# LED_base_left.net
KiCad netlist of a schematic drawn in EAGLE
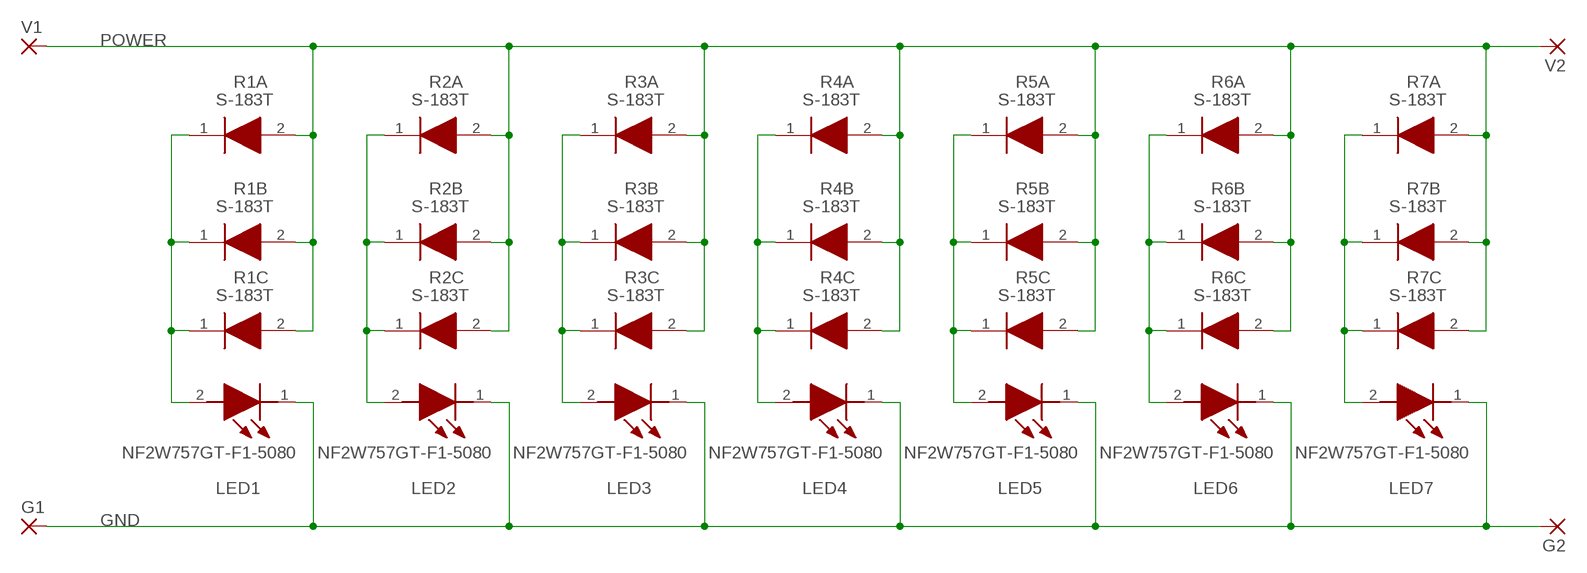
[diagram p0: schematic, sheet 1]

(export (version "E")
  (design (tool "Eeschema 10.0.6"))
  (components
    (comp (ref "G1")
      (value "SMD_FULL")
      (footprint "eagle-import:SMD3.5-2.5")
      (libsource (lib "eagle-import") (part "SMD_FULL"))
    )
    (comp (ref "G2")
      (value "SMD_HALF")
      (footprint "eagle-import:SMD1.75-2.5")
      (libsource (lib "eagle-import") (part "SMD_HALF"))
    )
    (comp (ref "LED1")
      (value "NF2W757GT-F1-5080")
      (footprint "eagle-import:NF2W757DRTX")
      (fields (field (name "RS_PART_NUMBER") "1372170"))
      (libsource (lib "eagle-import") (part "NF2W757GT-F1-5080"))
    )
    (comp (ref "LED2")
      (value "NF2W757GT-F1-5080")
      (footprint "eagle-import:NF2W757DRTX")
      (fields (field (name "RS_PART_NUMBER") "1372170"))
      (libsource (lib "eagle-import") (part "NF2W757GT-F1-5080"))
    )
    (comp (ref "LED3")
      (value "NF2W757GT-F1-5080")
      (footprint "eagle-import:NF2W757DRTX")
      (fields (field (name "RS_PART_NUMBER") "1372170"))
      (libsource (lib "eagle-import") (part "NF2W757GT-F1-5080"))
    )
    (comp (ref "LED4")
      (value "NF2W757GT-F1-5080")
      (footprint "eagle-import:NF2W757DRTX")
      (fields (field (name "RS_PART_NUMBER") "1372170"))
      (libsource (lib "eagle-import") (part "NF2W757GT-F1-5080"))
    )
    (comp (ref "LED5")
      (value "NF2W757GT-F1-5080")
      (footprint "eagle-import:NF2W757DRTX")
      (fields (field (name "RS_PART_NUMBER") "1372170"))
      (libsource (lib "eagle-import") (part "NF2W757GT-F1-5080"))
    )
    (comp (ref "LED6")
      (value "NF2W757GT-F1-5080")
      (footprint "eagle-import:NF2W757DRTX")
      (fields (field (name "RS_PART_NUMBER") "1372170"))
      (libsource (lib "eagle-import") (part "NF2W757GT-F1-5080"))
    )
    (comp (ref "LED7")
      (value "NF2W757GT-F1-5080")
      (footprint "eagle-import:NF2W757DRTX")
      (fields (field (name "RS_PART_NUMBER") "1372170"))
      (libsource (lib "eagle-import") (part "NF2W757GT-F1-5080"))
    )
    (comp (ref "R1A")
      (value "S-183T")
      (footprint "eagle-import:SODFL3516X70NX")
      (fields (field (name "MOUSER_PART_NUMBER") "954-S-183T"))
      (libsource (lib "eagle-import") (part "S-183T"))
    )
    (comp (ref "R1B")
      (value "S-183T")
      (footprint "eagle-import:SODFL3516X70NX")
      (fields (field (name "MOUSER_PART_NUMBER") "954-S-183T"))
      (libsource (lib "eagle-import") (part "S-183T"))
    )
    (comp (ref "R1C")
      (value "S-183T")
      (footprint "eagle-import:SODFL3516X70NX")
      (fields (field (name "MOUSER_PART_NUMBER") "954-S-183T"))
      (libsource (lib "eagle-import") (part "S-183T"))
    )
    (comp (ref "R2A")
      (value "S-183T")
      (footprint "eagle-import:SODFL3516X70NX")
      (fields (field (name "MOUSER_PART_NUMBER") "954-S-183T"))
      (libsource (lib "eagle-import") (part "S-183T"))
    )
    (comp (ref "R2B")
      (value "S-183T")
      (footprint "eagle-import:SODFL3516X70NX")
      (fields (field (name "MOUSER_PART_NUMBER") "954-S-183T"))
      (libsource (lib "eagle-import") (part "S-183T"))
    )
    (comp (ref "R2C")
      (value "S-183T")
      (footprint "eagle-import:SODFL3516X70NX")
      (fields (field (name "MOUSER_PART_NUMBER") "954-S-183T"))
      (libsource (lib "eagle-import") (part "S-183T"))
    )
    (comp (ref "R3A")
      (value "S-183T")
      (footprint "eagle-import:SODFL3516X70NX")
      (fields (field (name "MOUSER_PART_NUMBER") "954-S-183T"))
      (libsource (lib "eagle-import") (part "S-183T"))
    )
    (comp (ref "R3B")
      (value "S-183T")
      (footprint "eagle-import:SODFL3516X70NX")
      (fields (field (name "MOUSER_PART_NUMBER") "954-S-183T"))
      (libsource (lib "eagle-import") (part "S-183T"))
    )
    (comp (ref "R3C")
      (value "S-183T")
      (footprint "eagle-import:SODFL3516X70NX")
      (fields (field (name "MOUSER_PART_NUMBER") "954-S-183T"))
      (libsource (lib "eagle-import") (part "S-183T"))
    )
    (comp (ref "R4A")
      (value "S-183T")
      (footprint "eagle-import:SODFL3516X70NX")
      (fields (field (name "MOUSER_PART_NUMBER") "954-S-183T"))
      (libsource (lib "eagle-import") (part "S-183T"))
    )
    (comp (ref "R4B")
      (value "S-183T")
      (footprint "eagle-import:SODFL3516X70NX")
      (fields (field (name "MOUSER_PART_NUMBER") "954-S-183T"))
      (libsource (lib "eagle-import") (part "S-183T"))
    )
    (comp (ref "R4C")
      (value "S-183T")
      (footprint "eagle-import:SODFL3516X70NX")
      (fields (field (name "MOUSER_PART_NUMBER") "954-S-183T"))
      (libsource (lib "eagle-import") (part "S-183T"))
    )
    (comp (ref "R5A")
      (value "S-183T")
      (footprint "eagle-import:SODFL3516X70NX")
      (fields (field (name "MOUSER_PART_NUMBER") "954-S-183T"))
      (libsource (lib "eagle-import") (part "S-183T"))
    )
    (comp (ref "R5B")
      (value "S-183T")
      (footprint "eagle-import:SODFL3516X70NX")
      (fields (field (name "MOUSER_PART_NUMBER") "954-S-183T"))
      (libsource (lib "eagle-import") (part "S-183T"))
    )
    (comp (ref "R5C")
      (value "S-183T")
      (footprint "eagle-import:SODFL3516X70NX")
      (fields (field (name "MOUSER_PART_NUMBER") "954-S-183T"))
      (libsource (lib "eagle-import") (part "S-183T"))
    )
    (comp (ref "R6A")
      (value "S-183T")
      (footprint "eagle-import:SODFL3516X70NX")
      (fields (field (name "MOUSER_PART_NUMBER") "954-S-183T"))
      (libsource (lib "eagle-import") (part "S-183T"))
    )
    (comp (ref "R6B")
      (value "S-183T")
      (footprint "eagle-import:SODFL3516X70NX")
      (fields (field (name "MOUSER_PART_NUMBER") "954-S-183T"))
      (libsource (lib "eagle-import") (part "S-183T"))
    )
    (comp (ref "R6C")
      (value "S-183T")
      (footprint "eagle-import:SODFL3516X70NX")
      (fields (field (name "MOUSER_PART_NUMBER") "954-S-183T"))
      (libsource (lib "eagle-import") (part "S-183T"))
    )
    (comp (ref "R7A")
      (value "S-183T")
      (footprint "eagle-import:SODFL3516X70NX")
      (fields (field (name "MOUSER_PART_NUMBER") "954-S-183T"))
      (libsource (lib "eagle-import") (part "S-183T"))
    )
    (comp (ref "R7B")
      (value "S-183T")
      (footprint "eagle-import:SODFL3516X70NX")
      (fields (field (name "MOUSER_PART_NUMBER") "954-S-183T"))
      (libsource (lib "eagle-import") (part "S-183T"))
    )
    (comp (ref "R7C")
      (value "S-183T")
      (footprint "eagle-import:SODFL3516X70NX")
      (fields (field (name "MOUSER_PART_NUMBER") "954-S-183T"))
      (libsource (lib "eagle-import") (part "S-183T"))
    )
    (comp (ref "V1")
      (value "SMD_FULL")
      (footprint "eagle-import:SMD3.5-2.5")
      (libsource (lib "eagle-import") (part "SMD_FULL"))
    )
    (comp (ref "V2")
      (value "SMD_HALF")
      (footprint "eagle-import:SMD1.75-2.5")
      (libsource (lib "eagle-import") (part "SMD_HALF"))
    )
  )
  (nets
    (net (code "1") (name "/GND") (class "Default")
      (node (ref "G1") (pin "1") (pinfunction "P_1") (pintype "passive"))
      (node (ref "G2") (pin "1") (pinfunction "P_1") (pintype "passive"))
      (node (ref "LED1") (pin "1") (pinfunction "K_1") (pintype "bidirectional"))
      (node (ref "LED2") (pin "1") (pinfunction "K_1") (pintype "bidirectional"))
      (node (ref "LED3") (pin "1") (pinfunction "K_1") (pintype "bidirectional"))
      (node (ref "LED4") (pin "1") (pinfunction "K_1") (pintype "bidirectional"))
      (node (ref "LED5") (pin "1") (pinfunction "K_1") (pintype "bidirectional"))
      (node (ref "LED6") (pin "1") (pinfunction "K_1") (pintype "bidirectional"))
      (node (ref "LED7") (pin "1") (pinfunction "K_1") (pintype "bidirectional"))
    )
    (net (code "2") (name "/POWER") (class "Default")
      (node (ref "R1A") (pin "2") (pinfunction "A_2") (pintype "bidirectional"))
      (node (ref "R1B") (pin "2") (pinfunction "A_2") (pintype "bidirectional"))
      (node (ref "R1C") (pin "2") (pinfunction "A_2") (pintype "bidirectional"))
      (node (ref "R2A") (pin "2") (pinfunction "A_2") (pintype "bidirectional"))
      (node (ref "R2B") (pin "2") (pinfunction "A_2") (pintype "bidirectional"))
      (node (ref "R2C") (pin "2") (pinfunction "A_2") (pintype "bidirectional"))
      (node (ref "R3A") (pin "2") (pinfunction "A_2") (pintype "bidirectional"))
      (node (ref "R3B") (pin "2") (pinfunction "A_2") (pintype "bidirectional"))
      (node (ref "R3C") (pin "2") (pinfunction "A_2") (pintype "bidirectional"))
      (node (ref "R4A") (pin "2") (pinfunction "A_2") (pintype "bidirectional"))
      (node (ref "R4B") (pin "2") (pinfunction "A_2") (pintype "bidirectional"))
      (node (ref "R4C") (pin "2") (pinfunction "A_2") (pintype "bidirectional"))
      (node (ref "R5A") (pin "2") (pinfunction "A_2") (pintype "bidirectional"))
      (node (ref "R5B") (pin "2") (pinfunction "A_2") (pintype "bidirectional"))
      (node (ref "R5C") (pin "2") (pinfunction "A_2") (pintype "bidirectional"))
      (node (ref "R6A") (pin "2") (pinfunction "A_2") (pintype "bidirectional"))
      (node (ref "R6B") (pin "2") (pinfunction "A_2") (pintype "bidirectional"))
      (node (ref "R6C") (pin "2") (pinfunction "A_2") (pintype "bidirectional"))
      (node (ref "R7A") (pin "2") (pinfunction "A_2") (pintype "bidirectional"))
      (node (ref "R7B") (pin "2") (pinfunction "A_2") (pintype "bidirectional"))
      (node (ref "R7C") (pin "2") (pinfunction "A_2") (pintype "bidirectional"))
      (node (ref "V1") (pin "1") (pinfunction "P_1") (pintype "passive"))
      (node (ref "V2") (pin "1") (pinfunction "P_1") (pintype "passive"))
    )
    (net (code "3") (name "Net-(LED1-A)") (class "Default")
      (node (ref "LED1") (pin "2") (pinfunction "A_2") (pintype "bidirectional"))
      (node (ref "R1A") (pin "1") (pinfunction "K_1") (pintype "bidirectional"))
      (node (ref "R1B") (pin "1") (pinfunction "K_1") (pintype "bidirectional"))
      (node (ref "R1C") (pin "1") (pinfunction "K_1") (pintype "bidirectional"))
    )
    (net (code "4") (name "Net-(LED2-A)") (class "Default")
      (node (ref "LED2") (pin "2") (pinfunction "A_2") (pintype "bidirectional"))
      (node (ref "R2A") (pin "1") (pinfunction "K_1") (pintype "bidirectional"))
      (node (ref "R2B") (pin "1") (pinfunction "K_1") (pintype "bidirectional"))
      (node (ref "R2C") (pin "1") (pinfunction "K_1") (pintype "bidirectional"))
    )
    (net (code "5") (name "Net-(LED3-A)") (class "Default")
      (node (ref "LED3") (pin "2") (pinfunction "A_2") (pintype "bidirectional"))
      (node (ref "R3A") (pin "1") (pinfunction "K_1") (pintype "bidirectional"))
      (node (ref "R3B") (pin "1") (pinfunction "K_1") (pintype "bidirectional"))
      (node (ref "R3C") (pin "1") (pinfunction "K_1") (pintype "bidirectional"))
    )
    (net (code "6") (name "Net-(LED4-A)") (class "Default")
      (node (ref "LED4") (pin "2") (pinfunction "A_2") (pintype "bidirectional"))
      (node (ref "R4A") (pin "1") (pinfunction "K_1") (pintype "bidirectional"))
      (node (ref "R4B") (pin "1") (pinfunction "K_1") (pintype "bidirectional"))
      (node (ref "R4C") (pin "1") (pinfunction "K_1") (pintype "bidirectional"))
    )
    (net (code "7") (name "Net-(LED5-A)") (class "Default")
      (node (ref "LED5") (pin "2") (pinfunction "A_2") (pintype "bidirectional"))
      (node (ref "R5A") (pin "1") (pinfunction "K_1") (pintype "bidirectional"))
      (node (ref "R5B") (pin "1") (pinfunction "K_1") (pintype "bidirectional"))
      (node (ref "R5C") (pin "1") (pinfunction "K_1") (pintype "bidirectional"))
    )
    (net (code "8") (name "Net-(LED6-A)") (class "Default")
      (node (ref "LED6") (pin "2") (pinfunction "A_2") (pintype "bidirectional"))
      (node (ref "R6A") (pin "1") (pinfunction "K_1") (pintype "bidirectional"))
      (node (ref "R6B") (pin "1") (pinfunction "K_1") (pintype "bidirectional"))
      (node (ref "R6C") (pin "1") (pinfunction "K_1") (pintype "bidirectional"))
    )
    (net (code "9") (name "Net-(LED7-A)") (class "Default")
      (node (ref "LED7") (pin "2") (pinfunction "A_2") (pintype "bidirectional"))
      (node (ref "R7A") (pin "1") (pinfunction "K_1") (pintype "bidirectional"))
      (node (ref "R7B") (pin "1") (pinfunction "K_1") (pintype "bidirectional"))
      (node (ref "R7C") (pin "1") (pinfunction "K_1") (pintype "bidirectional"))
    )
  )
)
